# door_control.net
KiCad netlist of a schematic drawn in EAGLE
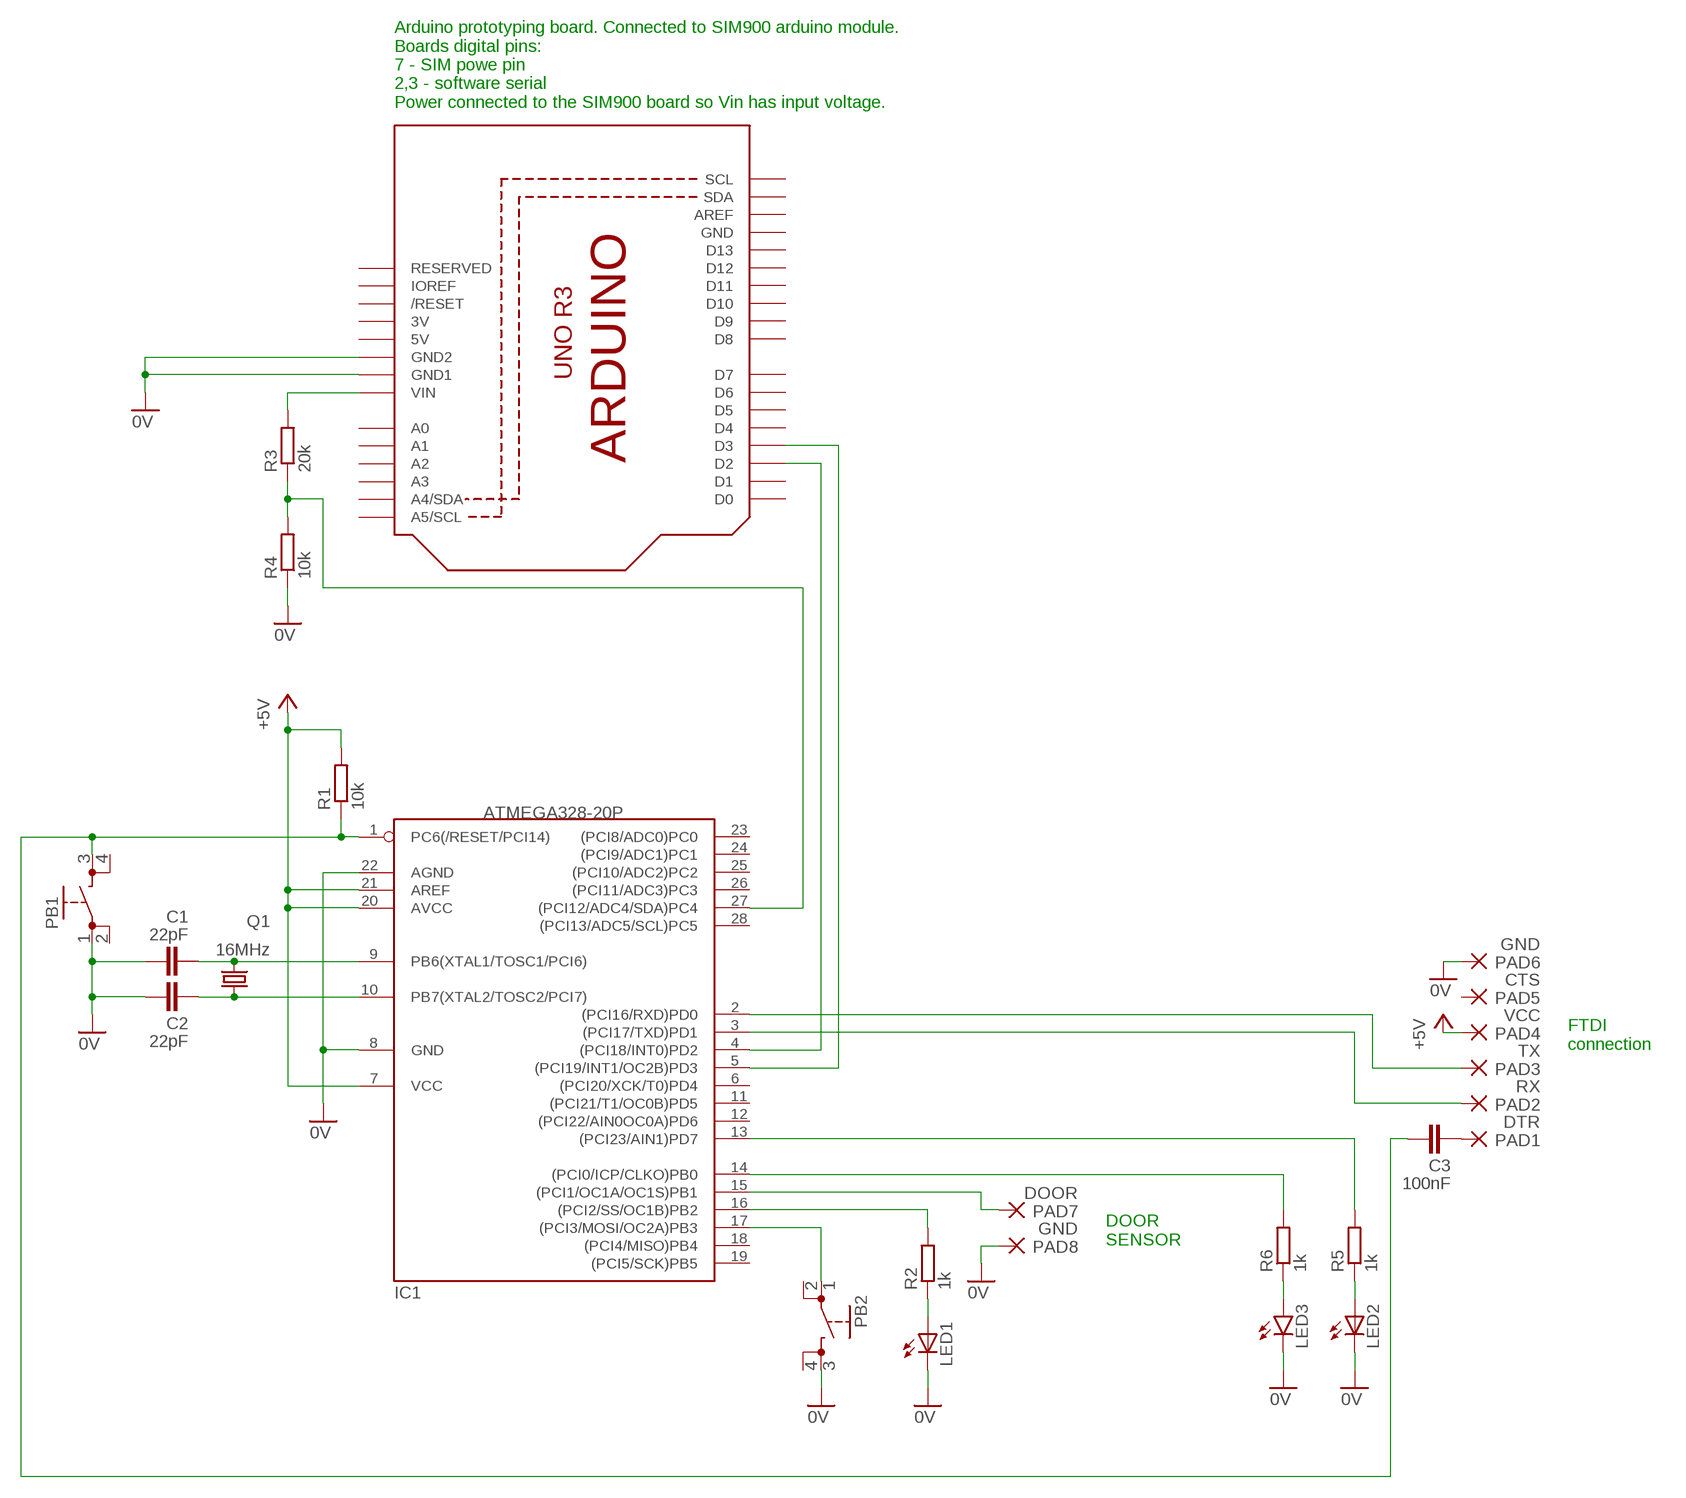
[diagram p0: schematic, sheet 1]

(export (version "E")
  (design (tool "Eeschema 10.0.6"))
  (components
    (comp (ref "C1")
      (value "22pF")
      (footprint "eagle-import:C5B2.5")
      (libsource (lib "eagle-import") (part "C5/2.5"))
    )
    (comp (ref "C2")
      (value "22pF")
      (footprint "eagle-import:C5B2.5")
      (libsource (lib "eagle-import") (part "C5/2.5"))
    )
    (comp (ref "C3")
      (value "100nF")
      (footprint "eagle-import:C10B4")
      (libsource (lib "eagle-import") (part "C10/4"))
    )
    (comp (ref "IC1")
      (value "ATMEGA328-20P")
      (footprint "eagle-import:DIL28-3")
      (libsource (lib "eagle-import") (part "ATMEGA328P-20"))
    )
    (comp (ref "LED1")
      (value "LED_ELD260")
      (footprint "eagle-import:LED_LD260")
      (libsource (lib "eagle-import") (part "LED_ELD260"))
    )
    (comp (ref "LED2")
      (value "LED_ELD260")
      (footprint "eagle-import:LED_LD260")
      (libsource (lib "eagle-import") (part "LED_ELD260"))
    )
    (comp (ref "LED3")
      (value "LED5MM")
      (footprint "eagle-import:LED5MM")
      (libsource (lib "eagle-import") (part "LED5MM"))
    )
    (comp (ref "PAD1")
      (value "DTR")
      (footprint "eagle-import:1,6_0,9")
      (libsource (lib "eagle-import") (part "1,6/0,9"))
    )
    (comp (ref "PAD2")
      (value "RX")
      (footprint "eagle-import:1,6_0,9")
      (libsource (lib "eagle-import") (part "1,6/0,9"))
    )
    (comp (ref "PAD3")
      (value "TX")
      (footprint "eagle-import:1,6_0,9")
      (libsource (lib "eagle-import") (part "1,6/0,9"))
    )
    (comp (ref "PAD4")
      (value "VCC")
      (footprint "eagle-import:1,6_0,9")
      (libsource (lib "eagle-import") (part "1,6/0,9"))
    )
    (comp (ref "PAD5")
      (value "CTS")
      (footprint "eagle-import:1,6_0,9")
      (libsource (lib "eagle-import") (part "1,6/0,9"))
    )
    (comp (ref "PAD6")
      (value "GND")
      (footprint "eagle-import:1,6_0,9")
      (libsource (lib "eagle-import") (part "1,6/0,9"))
    )
    (comp (ref "PAD7")
      (value "DOOR")
      (footprint "eagle-import:1,6_0,9")
      (libsource (lib "eagle-import") (part "1,6/0,9"))
    )
    (comp (ref "PAD8")
      (value "GND")
      (footprint "eagle-import:1,6_0,9")
      (libsource (lib "eagle-import") (part "1,6/0,9"))
    )
    (comp (ref "PB1")
      (value "4P_BUTTONTH")
      (footprint "eagle-import:4P_BUTTON")
      (libsource (lib "eagle-import") (part "4P_BUTTONTH"))
    )
    (comp (ref "PB2")
      (value "4P_BUTTONTH")
      (footprint "eagle-import:4P_BUTTON")
      (libsource (lib "eagle-import") (part "4P_BUTTONTH"))
    )
    (comp (ref "Q1")
      (value "16MHz")
      (footprint "eagle-import:HC49_S")
      (libsource (lib "eagle-import") (part "CRYSTALHC49S"))
    )
    (comp (ref "R1")
      (value "10k")
      (footprint "eagle-import:0207_10")
      (libsource (lib "eagle-import") (part "R-EU_0207/10"))
    )
    (comp (ref "R2")
      (value "1k")
      (footprint "eagle-import:0204_5")
      (libsource (lib "eagle-import") (part "R-EU_0204/5"))
    )
    (comp (ref "R3")
      (value "20k")
      (footprint "eagle-import:0204_5")
      (libsource (lib "eagle-import") (part "R-EU_0204/5"))
    )
    (comp (ref "R4")
      (value "10k")
      (footprint "eagle-import:0204_5")
      (libsource (lib "eagle-import") (part "R-EU_0204/5"))
    )
    (comp (ref "R5")
      (value "1k")
      (footprint "eagle-import:0204_5")
      (libsource (lib "eagle-import") (part "R-EU_0204/5"))
    )
    (comp (ref "R6")
      (value "1k")
      (footprint "eagle-import:0204_5")
      (libsource (lib "eagle-import") (part "R-EU_0204/5"))
    )
    (comp (ref "U1")
      (value "ARDUINOR3-DIMENSION")
      (footprint "eagle-import:ARDUINOR3")
      (libsource (lib "eagle-import") (part "ARDUINOR3-DIMENSION"))
    )
  )
  (nets
    (net (code "1") (name "+5V") (class "Default")
      (node (ref "IC1") (pin "20") (pinfunction "AVCC_20") (pintype "bidirectional"))
      (node (ref "IC1") (pin "21") (pinfunction "AREF_21") (pintype "bidirectional"))
      (node (ref "IC1") (pin "7") (pinfunction "VCC_7") (pintype "bidirectional"))
      (node (ref "PAD4") (pin "1") (pinfunction "P_1") (pintype "passive"))
      (node (ref "R1") (pin "2") (pinfunction "2_2") (pintype "passive"))
    )
    (net (code "2") (name "/3V") (class "Default")
      (node (ref "U1") (pin "3V") (pinfunction "3V_3V") (pintype "power_in"))
    )
    (net (code "3") (name "/5V") (class "Default")
      (node (ref "U1") (pin "5V") (pinfunction "5V_5V") (pintype "power_in"))
    )
    (net (code "4") (name "/GND") (class "Default")
      (node (ref "U1") (pin "GND") (pinfunction "GND_GND") (pintype "power_in"))
    )
    (net (code "5") (name "0V") (class "Default")
      (node (ref "C1") (pin "1") (pinfunction "1_1") (pintype "passive"))
      (node (ref "C2") (pin "1") (pinfunction "1_1") (pintype "passive"))
      (node (ref "IC1") (pin "22") (pinfunction "AGND_22") (pintype "bidirectional"))
      (node (ref "IC1") (pin "8") (pinfunction "GND_8") (pintype "bidirectional"))
      (node (ref "LED1") (pin "K") (pinfunction "C_K") (pintype "passive"))
      (node (ref "LED2") (pin "K") (pinfunction "C_K") (pintype "passive"))
      (node (ref "LED3") (pin "K") (pinfunction "C_K") (pintype "passive"))
      (node (ref "PAD6") (pin "1") (pinfunction "P_1") (pintype "passive"))
      (node (ref "PAD8") (pin "1") (pinfunction "P_1") (pintype "passive"))
      (node (ref "PB1") (pin "1") (pinfunction "1_1") (pintype "passive"))
      (node (ref "PB2") (pin "3") (pinfunction "3_3") (pintype "passive"))
      (node (ref "R4") (pin "1") (pinfunction "1_1") (pintype "passive"))
      (node (ref "U1") (pin "GND1") (pinfunction "GND1_GND1") (pintype "power_in"))
      (node (ref "U1") (pin "GND2") (pinfunction "GND2_GND2") (pintype "power_in"))
    )
    (net (code "6") (name "Net-(IC1-(PCI0{slash}ICP{slash}CLKO)PB0)") (class "Default")
      (node (ref "IC1") (pin "14") (pinfunction "(PCI0/ICP/CLKO)PB0_14") (pintype "bidirectional"))
      (node (ref "R6") (pin "2") (pinfunction "2_2") (pintype "passive"))
    )
    (net (code "7") (name "Net-(IC1-(PCI1{slash}OC1A{slash}OC1S)PB1)") (class "Default")
      (node (ref "IC1") (pin "15") (pinfunction "(PCI1/OC1A/OC1S)PB1_15") (pintype "bidirectional"))
      (node (ref "PAD7") (pin "1") (pinfunction "P_1") (pintype "passive"))
    )
    (net (code "8") (name "Net-(IC1-(PCI2{slash}SS{slash}OC1B)PB2)") (class "Default")
      (node (ref "IC1") (pin "16") (pinfunction "(PCI2/SS/OC1B)PB2_16") (pintype "bidirectional"))
      (node (ref "R2") (pin "2") (pinfunction "2_2") (pintype "passive"))
    )
    (net (code "9") (name "Net-(IC1-(PCI3{slash}MOSI{slash}OC2A)PB3)") (class "Default")
      (node (ref "IC1") (pin "17") (pinfunction "(PCI3/MOSI/OC2A)PB3_17") (pintype "bidirectional"))
      (node (ref "PB2") (pin "1") (pinfunction "1_1") (pintype "passive"))
    )
    (net (code "10") (name "Net-(IC1-(PCI12{slash}ADC4{slash}SDA)PC4)") (class "Default")
      (node (ref "IC1") (pin "27") (pinfunction "(PCI12/ADC4/SDA)PC4_27") (pintype "bidirectional"))
      (node (ref "R3") (pin "1") (pinfunction "1_1") (pintype "passive"))
      (node (ref "R4") (pin "2") (pinfunction "2_2") (pintype "passive"))
    )
    (net (code "11") (name "Net-(IC1-(PCI16{slash}RXD)PD0)") (class "Default")
      (node (ref "IC1") (pin "2") (pinfunction "(PCI16/RXD)PD0_2") (pintype "bidirectional"))
      (node (ref "PAD3") (pin "1") (pinfunction "P_1") (pintype "passive"))
    )
    (net (code "12") (name "Net-(IC1-(PCI17{slash}TXD)PD1)") (class "Default")
      (node (ref "IC1") (pin "3") (pinfunction "(PCI17/TXD)PD1_3") (pintype "bidirectional"))
      (node (ref "PAD2") (pin "1") (pinfunction "P_1") (pintype "passive"))
    )
    (net (code "13") (name "Net-(IC1-(PCI18{slash}INT0)PD2)") (class "Default")
      (node (ref "IC1") (pin "4") (pinfunction "(PCI18/INT0)PD2_4") (pintype "bidirectional"))
      (node (ref "U1") (pin "D2") (pinfunction "D2_D2") (pintype "bidirectional"))
    )
    (net (code "14") (name "Net-(IC1-(PCI19{slash}INT1{slash}OC2B)PD3)") (class "Default")
      (node (ref "IC1") (pin "5") (pinfunction "(PCI19/INT1/OC2B)PD3_5") (pintype "bidirectional"))
      (node (ref "U1") (pin "D3") (pinfunction "D3_D3") (pintype "bidirectional"))
    )
    (net (code "15") (name "Net-(IC1-(PCI23{slash}AIN1)PD7)") (class "Default")
      (node (ref "IC1") (pin "13") (pinfunction "(PCI23/AIN1)PD7_13") (pintype "bidirectional"))
      (node (ref "R5") (pin "2") (pinfunction "2_2") (pintype "passive"))
    )
    (net (code "16") (name "Net-(IC1-PB6(XTAL1{slash}TOSC1{slash}PCI6))") (class "Default")
      (node (ref "C1") (pin "2") (pinfunction "2_2") (pintype "passive"))
      (node (ref "IC1") (pin "9") (pinfunction "PB6(XTAL1/TOSC1/PCI6)_9") (pintype "bidirectional"))
      (node (ref "Q1") (pin "2") (pinfunction "2_2") (pintype "passive"))
    )
    (net (code "17") (name "Net-(IC1-PB7(XTAL2{slash}TOSC2{slash}PCI7))") (class "Default")
      (node (ref "C2") (pin "2") (pinfunction "2_2") (pintype "passive"))
      (node (ref "IC1") (pin "10") (pinfunction "PB7(XTAL2/TOSC2/PCI7)_10") (pintype "bidirectional"))
      (node (ref "Q1") (pin "1") (pinfunction "1_1") (pintype "passive"))
    )
    (net (code "18") (name "Net-(IC1-PC6({slash}RESET{slash}PCI14))") (class "Default")
      (node (ref "C3") (pin "1") (pinfunction "1_1") (pintype "passive"))
      (node (ref "IC1") (pin "1") (pinfunction "PC6(/RESET/PCI14)_1") (pintype "bidirectional"))
      (node (ref "PB1") (pin "3") (pinfunction "3_3") (pintype "passive"))
      (node (ref "R1") (pin "1") (pinfunction "1_1") (pintype "passive"))
    )
    (net (code "19") (name "Net-(LED1-PadA)") (class "Default")
      (node (ref "LED1") (pin "A") (pinfunction "A_A") (pintype "passive"))
      (node (ref "R2") (pin "1") (pinfunction "1_1") (pintype "passive"))
    )
    (net (code "20") (name "Net-(LED2-PadA)") (class "Default")
      (node (ref "LED2") (pin "A") (pinfunction "A_A") (pintype "passive"))
      (node (ref "R5") (pin "1") (pinfunction "1_1") (pintype "passive"))
    )
    (net (code "21") (name "Net-(LED3-PadA)") (class "Default")
      (node (ref "LED3") (pin "A") (pinfunction "A_A") (pintype "passive"))
      (node (ref "R6") (pin "1") (pinfunction "1_1") (pintype "passive"))
    )
    (net (code "22") (name "Net-(PAD1-P)") (class "Default")
      (node (ref "C3") (pin "2") (pinfunction "2_2") (pintype "passive"))
      (node (ref "PAD1") (pin "1") (pinfunction "P_1") (pintype "passive"))
    )
    (net (code "23") (name "Net-(R3-Pad2)") (class "Default")
      (node (ref "R3") (pin "2") (pinfunction "2_2") (pintype "passive"))
      (node (ref "U1") (pin "VIN") (pinfunction "VIN_VIN") (pintype "power_in"))
    )
    (net (code "24") (name "unconnected-(IC1-(PCI4{slash}MISO)PB4-Pad18)") (class "Default")
      (node (ref "IC1") (pin "18") (pinfunction "(PCI4/MISO)PB4_18") (pintype "bidirectional"))
    )
    (net (code "25") (name "unconnected-(IC1-(PCI5{slash}SCK)PB5-Pad19)") (class "Default")
      (node (ref "IC1") (pin "19") (pinfunction "(PCI5/SCK)PB5_19") (pintype "bidirectional"))
    )
    (net (code "26") (name "unconnected-(IC1-(PCI8{slash}ADC0)PC0-Pad23)") (class "Default")
      (node (ref "IC1") (pin "23") (pinfunction "(PCI8/ADC0)PC0_23") (pintype "bidirectional"))
    )
    (net (code "27") (name "unconnected-(IC1-(PCI9{slash}ADC1)PC1-Pad24)") (class "Default")
      (node (ref "IC1") (pin "24") (pinfunction "(PCI9/ADC1)PC1_24") (pintype "bidirectional"))
    )
    (net (code "28") (name "unconnected-(IC1-(PCI10{slash}ADC2)PC2-Pad25)") (class "Default")
      (node (ref "IC1") (pin "25") (pinfunction "(PCI10/ADC2)PC2_25") (pintype "bidirectional"))
    )
    (net (code "29") (name "unconnected-(IC1-(PCI11{slash}ADC3)PC3-Pad26)") (class "Default")
      (node (ref "IC1") (pin "26") (pinfunction "(PCI11/ADC3)PC3_26") (pintype "bidirectional"))
    )
    (net (code "30") (name "unconnected-(IC1-(PCI13{slash}ADC5{slash}SCL)PC5-Pad28)") (class "Default")
      (node (ref "IC1") (pin "28") (pinfunction "(PCI13/ADC5/SCL)PC5_28") (pintype "bidirectional"))
    )
    (net (code "31") (name "unconnected-(IC1-(PCI20{slash}XCK{slash}T0)PD4-Pad6)") (class "Default")
      (node (ref "IC1") (pin "6") (pinfunction "(PCI20/XCK/T0)PD4_6") (pintype "bidirectional"))
    )
    (net (code "32") (name "unconnected-(IC1-(PCI21{slash}T1{slash}OC0B)PD5-Pad11)") (class "Default")
      (node (ref "IC1") (pin "11") (pinfunction "(PCI21/T1/OC0B)PD5_11") (pintype "bidirectional"))
    )
    (net (code "33") (name "unconnected-(IC1-(PCI22{slash}AIN0OC0A)PD6-Pad12)") (class "Default")
      (node (ref "IC1") (pin "12") (pinfunction "(PCI22/AIN0OC0A)PD6_12") (pintype "bidirectional"))
    )
    (net (code "34") (name "unconnected-(PAD5-P-Pad1)") (class "Default")
      (node (ref "PAD5") (pin "1") (pinfunction "P_1") (pintype "passive"))
    )
    (net (code "35") (name "unconnected-(PB1-Pad2)") (class "Default")
      (node (ref "PB1") (pin "2") (pinfunction "2_2") (pintype "passive"))
    )
    (net (code "36") (name "unconnected-(PB1-Pad4)") (class "Default")
      (node (ref "PB1") (pin "4") (pinfunction "4_4") (pintype "passive"))
    )
    (net (code "37") (name "unconnected-(PB2-Pad2)") (class "Default")
      (node (ref "PB2") (pin "2") (pinfunction "2_2") (pintype "passive"))
    )
    (net (code "38") (name "unconnected-(PB2-Pad4)") (class "Default")
      (node (ref "PB2") (pin "4") (pinfunction "4_4") (pintype "passive"))
    )
    (net (code "39") (name "unconnected-(U1-A4{slash}SDA-PadA4)") (class "Default")
      (node (ref "U1") (pin "A4") (pinfunction "A4/SDA_A4") (pintype "bidirectional"))
    )
    (net (code "40") (name "unconnected-(U1-A5{slash}SCL-PadA5)") (class "Default")
      (node (ref "U1") (pin "A5") (pinfunction "A5/SCL_A5") (pintype "bidirectional"))
    )
    (net (code "41") (name "unconnected-(U1-PadA0)") (class "Default")
      (node (ref "U1") (pin "A0") (pinfunction "A0_A0") (pintype "bidirectional"))
    )
    (net (code "42") (name "unconnected-(U1-PadA1)") (class "Default")
      (node (ref "U1") (pin "A1") (pinfunction "A1_A1") (pintype "bidirectional"))
    )
    (net (code "43") (name "unconnected-(U1-PadA2)") (class "Default")
      (node (ref "U1") (pin "A2") (pinfunction "A2_A2") (pintype "bidirectional"))
    )
    (net (code "44") (name "unconnected-(U1-PadA3)") (class "Default")
      (node (ref "U1") (pin "A3") (pinfunction "A3_A3") (pintype "bidirectional"))
    )
    (net (code "45") (name "unconnected-(U1-PadAREF)") (class "Default")
      (node (ref "U1") (pin "AREF") (pinfunction "AREF_AREF") (pintype "bidirectional"))
    )
    (net (code "46") (name "unconnected-(U1-PadD0)") (class "Default")
      (node (ref "U1") (pin "D0") (pinfunction "D0_D0") (pintype "bidirectional"))
    )
    (net (code "47") (name "unconnected-(U1-PadD1)") (class "Default")
      (node (ref "U1") (pin "D1") (pinfunction "D1_D1") (pintype "bidirectional"))
    )
    (net (code "48") (name "unconnected-(U1-PadD4)") (class "Default")
      (node (ref "U1") (pin "D4") (pinfunction "D4_D4") (pintype "bidirectional"))
    )
    (net (code "49") (name "unconnected-(U1-PadD5)") (class "Default")
      (node (ref "U1") (pin "D5") (pinfunction "D5_D5") (pintype "bidirectional"))
    )
    (net (code "50") (name "unconnected-(U1-PadD6)") (class "Default")
      (node (ref "U1") (pin "D6") (pinfunction "D6_D6") (pintype "bidirectional"))
    )
    (net (code "51") (name "unconnected-(U1-PadD7)") (class "Default")
      (node (ref "U1") (pin "D7") (pinfunction "D7_D7") (pintype "bidirectional"))
    )
    (net (code "52") (name "unconnected-(U1-PadD8)") (class "Default")
      (node (ref "U1") (pin "D8") (pinfunction "D8_D8") (pintype "bidirectional"))
    )
    (net (code "53") (name "unconnected-(U1-PadD9)") (class "Default")
      (node (ref "U1") (pin "D9") (pinfunction "D9_D9") (pintype "bidirectional"))
    )
    (net (code "54") (name "unconnected-(U1-PadD10)") (class "Default")
      (node (ref "U1") (pin "D10") (pinfunction "D10_D10") (pintype "bidirectional"))
    )
    (net (code "55") (name "unconnected-(U1-PadD11)") (class "Default")
      (node (ref "U1") (pin "D11") (pinfunction "D11_D11") (pintype "bidirectional"))
    )
    (net (code "56") (name "unconnected-(U1-PadD12)") (class "Default")
      (node (ref "U1") (pin "D12") (pinfunction "D12_D12") (pintype "bidirectional"))
    )
    (net (code "57") (name "unconnected-(U1-PadD13)") (class "Default")
      (node (ref "U1") (pin "D13") (pinfunction "D13_D13") (pintype "bidirectional"))
    )
    (net (code "58") (name "unconnected-(U1-PadIOREF)") (class "Default")
      (node (ref "U1") (pin "IOREF") (pinfunction "IOREF_IOREF") (pintype "output"))
    )
    (net (code "59") (name "unconnected-(U1-PadRESERVED)") (class "Default")
      (node (ref "U1") (pin "RESERVED") (pinfunction "RESERVED_RESERVED") (pintype "no_connect"))
    )
    (net (code "60") (name "unconnected-(U1-PadSCL)") (class "Default")
      (node (ref "U1") (pin "SCL") (pinfunction "SCL_SCL") (pintype "bidirectional"))
    )
    (net (code "61") (name "unconnected-(U1-PadSDA)") (class "Default")
      (node (ref "U1") (pin "SDA") (pinfunction "SDA_SDA") (pintype "bidirectional"))
    )
    (net (code "62") (name "unconnected-(U1-{slash}RESET-PadRESET)") (class "Default")
      (node (ref "U1") (pin "RESET") (pinfunction "/RESET_RESET") (pintype "bidirectional"))
    )
  )
)
